# Z7_MGTX.net
KiCad netlist of a schematic drawn in Altium Designer
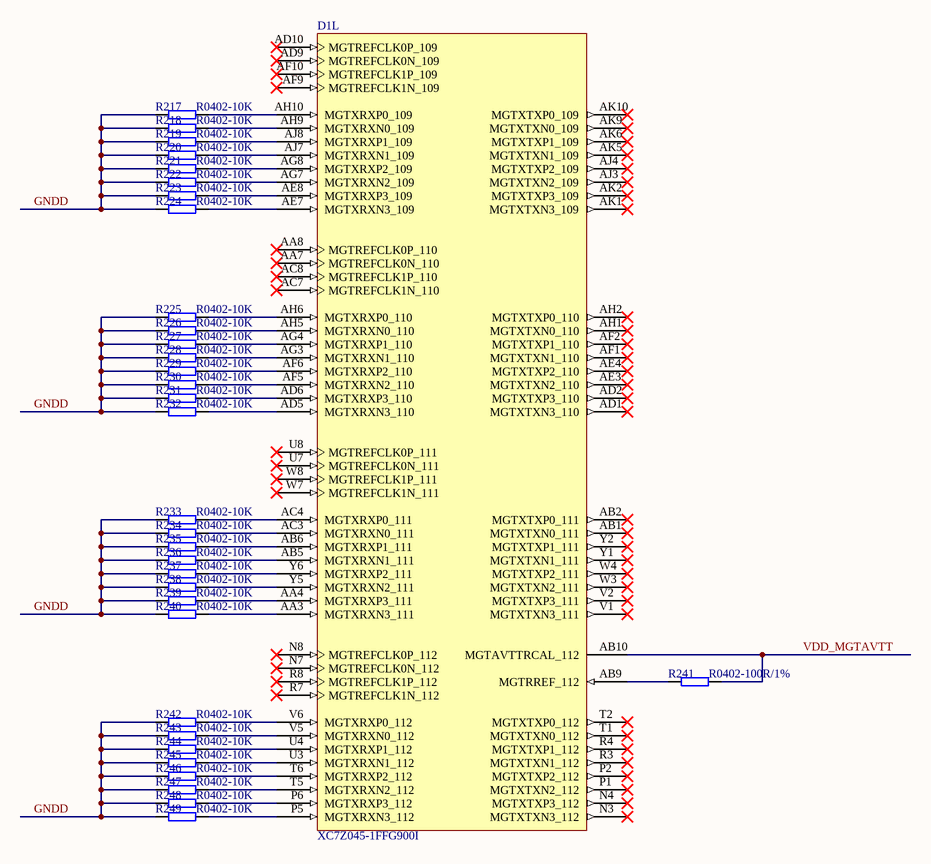
[diagram p0: Z7_MGTX.SchDoc]

(export (version "E")
  (design (tool "Eeschema 10.0.6"))
  (components
    (comp (ref "D1")
      (value "XC7Z045-1FFG900I")
      (footprint "FFG900")
      (fields (field (name "GENERIC PART NUMBER") "XC7Z045") (field (name "MANUFACTURER") "Xilinx"))
      (libsource (lib "Xilinx Zynq-7000") (part "XC7Z045-1FFG900I"))
    )
    (comp (ref "R217")
      (value "R0402-10K")
      (footprint "R0402")
      (fields (field (name "SCHEMATIC_PART") "RES") (field (name "MANUFACTURER") "SAMSUNG"))
      (libsource (lib "Database_Libs1") (part "RES"))
    )
    (comp (ref "R218")
      (value "R0402-10K")
      (footprint "R0402")
      (fields (field (name "SCHEMATIC_PART") "RES") (field (name "MANUFACTURER") "SAMSUNG"))
      (libsource (lib "Database_Libs1") (part "RES"))
    )
    (comp (ref "R219")
      (value "R0402-10K")
      (footprint "R0402")
      (fields (field (name "SCHEMATIC_PART") "RES") (field (name "MANUFACTURER") "SAMSUNG"))
      (libsource (lib "Database_Libs1") (part "RES"))
    )
    (comp (ref "R220")
      (value "R0402-10K")
      (footprint "R0402")
      (fields (field (name "SCHEMATIC_PART") "RES") (field (name "MANUFACTURER") "SAMSUNG"))
      (libsource (lib "Database_Libs1") (part "RES"))
    )
    (comp (ref "R221")
      (value "R0402-10K")
      (footprint "R0402")
      (fields (field (name "SCHEMATIC_PART") "RES") (field (name "MANUFACTURER") "SAMSUNG"))
      (libsource (lib "Database_Libs1") (part "RES"))
    )
    (comp (ref "R222")
      (value "R0402-10K")
      (footprint "R0402")
      (fields (field (name "SCHEMATIC_PART") "RES") (field (name "MANUFACTURER") "SAMSUNG"))
      (libsource (lib "Database_Libs1") (part "RES"))
    )
    (comp (ref "R223")
      (value "R0402-10K")
      (footprint "R0402")
      (fields (field (name "SCHEMATIC_PART") "RES") (field (name "MANUFACTURER") "SAMSUNG"))
      (libsource (lib "Database_Libs1") (part "RES"))
    )
    (comp (ref "R224")
      (value "R0402-10K")
      (footprint "R0402")
      (fields (field (name "SCHEMATIC_PART") "RES") (field (name "MANUFACTURER") "SAMSUNG"))
      (libsource (lib "Database_Libs1") (part "RES"))
    )
    (comp (ref "R225")
      (value "R0402-10K")
      (footprint "R0402")
      (fields (field (name "SCHEMATIC_PART") "RES") (field (name "MANUFACTURER") "SAMSUNG"))
      (libsource (lib "Database_Libs1") (part "RES"))
    )
    (comp (ref "R226")
      (value "R0402-10K")
      (footprint "R0402")
      (fields (field (name "SCHEMATIC_PART") "RES") (field (name "MANUFACTURER") "SAMSUNG"))
      (libsource (lib "Database_Libs1") (part "RES"))
    )
    (comp (ref "R227")
      (value "R0402-10K")
      (footprint "R0402")
      (fields (field (name "SCHEMATIC_PART") "RES") (field (name "MANUFACTURER") "SAMSUNG"))
      (libsource (lib "Database_Libs1") (part "RES"))
    )
    (comp (ref "R228")
      (value "R0402-10K")
      (footprint "R0402")
      (fields (field (name "SCHEMATIC_PART") "RES") (field (name "MANUFACTURER") "SAMSUNG"))
      (libsource (lib "Database_Libs1") (part "RES"))
    )
    (comp (ref "R229")
      (value "R0402-10K")
      (footprint "R0402")
      (fields (field (name "SCHEMATIC_PART") "RES") (field (name "MANUFACTURER") "SAMSUNG"))
      (libsource (lib "Database_Libs1") (part "RES"))
    )
    (comp (ref "R230")
      (value "R0402-10K")
      (footprint "R0402")
      (fields (field (name "SCHEMATIC_PART") "RES") (field (name "MANUFACTURER") "SAMSUNG"))
      (libsource (lib "Database_Libs1") (part "RES"))
    )
    (comp (ref "R231")
      (value "R0402-10K")
      (footprint "R0402")
      (fields (field (name "SCHEMATIC_PART") "RES") (field (name "MANUFACTURER") "SAMSUNG"))
      (libsource (lib "Database_Libs1") (part "RES"))
    )
    (comp (ref "R232")
      (value "R0402-10K")
      (footprint "R0402")
      (fields (field (name "SCHEMATIC_PART") "RES") (field (name "MANUFACTURER") "SAMSUNG"))
      (libsource (lib "Database_Libs1") (part "RES"))
    )
    (comp (ref "R233")
      (value "R0402-10K")
      (footprint "R0402")
      (fields (field (name "SCHEMATIC_PART") "RES") (field (name "MANUFACTURER") "SAMSUNG"))
      (libsource (lib "Database_Libs1") (part "RES"))
    )
    (comp (ref "R234")
      (value "R0402-10K")
      (footprint "R0402")
      (fields (field (name "SCHEMATIC_PART") "RES") (field (name "MANUFACTURER") "SAMSUNG"))
      (libsource (lib "Database_Libs1") (part "RES"))
    )
    (comp (ref "R235")
      (value "R0402-10K")
      (footprint "R0402")
      (fields (field (name "SCHEMATIC_PART") "RES") (field (name "MANUFACTURER") "SAMSUNG"))
      (libsource (lib "Database_Libs1") (part "RES"))
    )
    (comp (ref "R236")
      (value "R0402-10K")
      (footprint "R0402")
      (fields (field (name "SCHEMATIC_PART") "RES") (field (name "MANUFACTURER") "SAMSUNG"))
      (libsource (lib "Database_Libs1") (part "RES"))
    )
    (comp (ref "R237")
      (value "R0402-10K")
      (footprint "R0402")
      (fields (field (name "SCHEMATIC_PART") "RES") (field (name "MANUFACTURER") "SAMSUNG"))
      (libsource (lib "Database_Libs1") (part "RES"))
    )
    (comp (ref "R238")
      (value "R0402-10K")
      (footprint "R0402")
      (fields (field (name "SCHEMATIC_PART") "RES") (field (name "MANUFACTURER") "SAMSUNG"))
      (libsource (lib "Database_Libs1") (part "RES"))
    )
    (comp (ref "R239")
      (value "R0402-10K")
      (footprint "R0402")
      (fields (field (name "SCHEMATIC_PART") "RES") (field (name "MANUFACTURER") "SAMSUNG"))
      (libsource (lib "Database_Libs1") (part "RES"))
    )
    (comp (ref "R240")
      (value "R0402-10K")
      (footprint "R0402")
      (fields (field (name "SCHEMATIC_PART") "RES") (field (name "MANUFACTURER") "SAMSUNG"))
      (libsource (lib "Database_Libs1") (part "RES"))
    )
    (comp (ref "R241")
      (value "R0402-100R/1%")
      (footprint "R0402")
      (fields (field (name "SCHEMATIC_PART") "RES") (field (name "MANUFACTURER") "SAMSUNG"))
      (libsource (lib "Database_Libs1") (part "RES"))
    )
    (comp (ref "R242")
      (value "R0402-10K")
      (footprint "R0402")
      (fields (field (name "SCHEMATIC_PART") "RES") (field (name "MANUFACTURER") "SAMSUNG"))
      (libsource (lib "Database_Libs1") (part "RES"))
    )
    (comp (ref "R243")
      (value "R0402-10K")
      (footprint "R0402")
      (fields (field (name "SCHEMATIC_PART") "RES") (field (name "MANUFACTURER") "SAMSUNG"))
      (libsource (lib "Database_Libs1") (part "RES"))
    )
    (comp (ref "R244")
      (value "R0402-10K")
      (footprint "R0402")
      (fields (field (name "SCHEMATIC_PART") "RES") (field (name "MANUFACTURER") "SAMSUNG"))
      (libsource (lib "Database_Libs1") (part "RES"))
    )
    (comp (ref "R245")
      (value "R0402-10K")
      (footprint "R0402")
      (fields (field (name "SCHEMATIC_PART") "RES") (field (name "MANUFACTURER") "SAMSUNG"))
      (libsource (lib "Database_Libs1") (part "RES"))
    )
    (comp (ref "R246")
      (value "R0402-10K")
      (footprint "R0402")
      (fields (field (name "SCHEMATIC_PART") "RES") (field (name "MANUFACTURER") "SAMSUNG"))
      (libsource (lib "Database_Libs1") (part "RES"))
    )
    (comp (ref "R247")
      (value "R0402-10K")
      (footprint "R0402")
      (fields (field (name "SCHEMATIC_PART") "RES") (field (name "MANUFACTURER") "SAMSUNG"))
      (libsource (lib "Database_Libs1") (part "RES"))
    )
    (comp (ref "R248")
      (value "R0402-10K")
      (footprint "R0402")
      (fields (field (name "SCHEMATIC_PART") "RES") (field (name "MANUFACTURER") "SAMSUNG"))
      (libsource (lib "Database_Libs1") (part "RES"))
    )
    (comp (ref "R249")
      (value "R0402-10K")
      (footprint "R0402")
      (fields (field (name "SCHEMATIC_PART") "RES") (field (name "MANUFACTURER") "SAMSUNG"))
      (libsource (lib "Database_Libs1") (part "RES"))
    )
  )
  (nets
    (net (code "1") (name "/GNDD") (class "Default")
      (node (ref "R217") (pin "2") (pintype "passive"))
      (node (ref "R218") (pin "2") (pintype "passive"))
      (node (ref "R219") (pin "2") (pintype "passive"))
      (node (ref "R220") (pin "2") (pintype "passive"))
      (node (ref "R221") (pin "2") (pintype "passive"))
      (node (ref "R222") (pin "2") (pintype "passive"))
      (node (ref "R223") (pin "2") (pintype "passive"))
      (node (ref "R224") (pin "2") (pintype "passive"))
      (node (ref "R225") (pin "2") (pintype "passive"))
      (node (ref "R226") (pin "2") (pintype "passive"))
      (node (ref "R227") (pin "2") (pintype "passive"))
      (node (ref "R228") (pin "2") (pintype "passive"))
      (node (ref "R229") (pin "2") (pintype "passive"))
      (node (ref "R230") (pin "2") (pintype "passive"))
      (node (ref "R231") (pin "2") (pintype "passive"))
      (node (ref "R232") (pin "2") (pintype "passive"))
      (node (ref "R233") (pin "2") (pintype "passive"))
      (node (ref "R234") (pin "2") (pintype "passive"))
      (node (ref "R235") (pin "2") (pintype "passive"))
      (node (ref "R236") (pin "2") (pintype "passive"))
      (node (ref "R237") (pin "2") (pintype "passive"))
      (node (ref "R238") (pin "2") (pintype "passive"))
      (node (ref "R239") (pin "2") (pintype "passive"))
      (node (ref "R240") (pin "2") (pintype "passive"))
      (node (ref "R242") (pin "2") (pintype "passive"))
      (node (ref "R243") (pin "2") (pintype "passive"))
      (node (ref "R244") (pin "2") (pintype "passive"))
      (node (ref "R245") (pin "2") (pintype "passive"))
      (node (ref "R246") (pin "2") (pintype "passive"))
      (node (ref "R247") (pin "2") (pintype "passive"))
      (node (ref "R248") (pin "2") (pintype "passive"))
      (node (ref "R249") (pin "2") (pintype "passive"))
    )
    (net (code "2") (name "/VDD_MGTAVTT") (class "Default")
      (node (ref "D1") (pin "AB10") (pinfunction "MGTAVTTRCAL_112_AB10") (pintype "passive"))
      (node (ref "R241") (pin "1") (pintype "passive"))
    )
    (net (code "3") (name "Net-(D1L-MGTRREF_112)") (class "Default")
      (node (ref "D1") (pin "AB9") (pinfunction "MGTRREF_112_AB9") (pintype "input"))
      (node (ref "R241") (pin "2") (pintype "passive"))
    )
    (net (code "4") (name "Net-(D1L-MGTXRXN0_109)") (class "Default")
      (node (ref "D1") (pin "AH9") (pinfunction "MGTXRXN0_109_AH9") (pintype "input"))
      (node (ref "R218") (pin "1") (pintype "passive"))
    )
    (net (code "5") (name "Net-(D1L-MGTXRXN0_110)") (class "Default")
      (node (ref "D1") (pin "AH5") (pinfunction "MGTXRXN0_110_AH5") (pintype "input"))
      (node (ref "R226") (pin "1") (pintype "passive"))
    )
    (net (code "6") (name "Net-(D1L-MGTXRXN0_111)") (class "Default")
      (node (ref "D1") (pin "AC3") (pinfunction "MGTXRXN0_111_AC3") (pintype "input"))
      (node (ref "R234") (pin "1") (pintype "passive"))
    )
    (net (code "7") (name "Net-(D1L-MGTXRXN0_112)") (class "Default")
      (node (ref "D1") (pin "V5") (pinfunction "MGTXRXN0_112_V5") (pintype "input"))
      (node (ref "R243") (pin "1") (pintype "passive"))
    )
    (net (code "8") (name "Net-(D1L-MGTXRXN1_109)") (class "Default")
      (node (ref "D1") (pin "AJ7") (pinfunction "MGTXRXN1_109_AJ7") (pintype "input"))
      (node (ref "R220") (pin "1") (pintype "passive"))
    )
    (net (code "9") (name "Net-(D1L-MGTXRXN1_110)") (class "Default")
      (node (ref "D1") (pin "AG3") (pinfunction "MGTXRXN1_110_AG3") (pintype "input"))
      (node (ref "R228") (pin "1") (pintype "passive"))
    )
    (net (code "10") (name "Net-(D1L-MGTXRXN1_111)") (class "Default")
      (node (ref "D1") (pin "AB5") (pinfunction "MGTXRXN1_111_AB5") (pintype "input"))
      (node (ref "R236") (pin "1") (pintype "passive"))
    )
    (net (code "11") (name "Net-(D1L-MGTXRXN1_112)") (class "Default")
      (node (ref "D1") (pin "U3") (pinfunction "MGTXRXN1_112_U3") (pintype "input"))
      (node (ref "R245") (pin "1") (pintype "passive"))
    )
    (net (code "12") (name "Net-(D1L-MGTXRXN2_109)") (class "Default")
      (node (ref "D1") (pin "AG7") (pinfunction "MGTXRXN2_109_AG7") (pintype "input"))
      (node (ref "R222") (pin "1") (pintype "passive"))
    )
    (net (code "13") (name "Net-(D1L-MGTXRXN2_110)") (class "Default")
      (node (ref "D1") (pin "AF5") (pinfunction "MGTXRXN2_110_AF5") (pintype "input"))
      (node (ref "R230") (pin "1") (pintype "passive"))
    )
    (net (code "14") (name "Net-(D1L-MGTXRXN2_111)") (class "Default")
      (node (ref "D1") (pin "Y5") (pinfunction "MGTXRXN2_111_Y5") (pintype "input"))
      (node (ref "R238") (pin "1") (pintype "passive"))
    )
    (net (code "15") (name "Net-(D1L-MGTXRXN2_112)") (class "Default")
      (node (ref "D1") (pin "T5") (pinfunction "MGTXRXN2_112_T5") (pintype "input"))
      (node (ref "R247") (pin "1") (pintype "passive"))
    )
    (net (code "16") (name "Net-(D1L-MGTXRXN3_109)") (class "Default")
      (node (ref "D1") (pin "AE7") (pinfunction "MGTXRXN3_109_AE7") (pintype "input"))
      (node (ref "R224") (pin "1") (pintype "passive"))
    )
    (net (code "17") (name "Net-(D1L-MGTXRXN3_110)") (class "Default")
      (node (ref "D1") (pin "AD5") (pinfunction "MGTXRXN3_110_AD5") (pintype "input"))
      (node (ref "R232") (pin "1") (pintype "passive"))
    )
    (net (code "18") (name "Net-(D1L-MGTXRXN3_111)") (class "Default")
      (node (ref "D1") (pin "AA3") (pinfunction "MGTXRXN3_111_AA3") (pintype "input"))
      (node (ref "R240") (pin "1") (pintype "passive"))
    )
    (net (code "19") (name "Net-(D1L-MGTXRXN3_112)") (class "Default")
      (node (ref "D1") (pin "P5") (pinfunction "MGTXRXN3_112_P5") (pintype "input"))
      (node (ref "R249") (pin "1") (pintype "passive"))
    )
    (net (code "20") (name "Net-(D1L-MGTXRXP0_109)") (class "Default")
      (node (ref "D1") (pin "AH10") (pinfunction "MGTXRXP0_109_AH10") (pintype "input"))
      (node (ref "R217") (pin "1") (pintype "passive"))
    )
    (net (code "21") (name "Net-(D1L-MGTXRXP0_110)") (class "Default")
      (node (ref "D1") (pin "AH6") (pinfunction "MGTXRXP0_110_AH6") (pintype "input"))
      (node (ref "R225") (pin "1") (pintype "passive"))
    )
    (net (code "22") (name "Net-(D1L-MGTXRXP0_111)") (class "Default")
      (node (ref "D1") (pin "AC4") (pinfunction "MGTXRXP0_111_AC4") (pintype "input"))
      (node (ref "R233") (pin "1") (pintype "passive"))
    )
    (net (code "23") (name "Net-(D1L-MGTXRXP0_112)") (class "Default")
      (node (ref "D1") (pin "V6") (pinfunction "MGTXRXP0_112_V6") (pintype "input"))
      (node (ref "R242") (pin "1") (pintype "passive"))
    )
    (net (code "24") (name "Net-(D1L-MGTXRXP1_109)") (class "Default")
      (node (ref "D1") (pin "AJ8") (pinfunction "MGTXRXP1_109_AJ8") (pintype "input"))
      (node (ref "R219") (pin "1") (pintype "passive"))
    )
    (net (code "25") (name "Net-(D1L-MGTXRXP1_110)") (class "Default")
      (node (ref "D1") (pin "AG4") (pinfunction "MGTXRXP1_110_AG4") (pintype "input"))
      (node (ref "R227") (pin "1") (pintype "passive"))
    )
    (net (code "26") (name "Net-(D1L-MGTXRXP1_111)") (class "Default")
      (node (ref "D1") (pin "AB6") (pinfunction "MGTXRXP1_111_AB6") (pintype "input"))
      (node (ref "R235") (pin "1") (pintype "passive"))
    )
    (net (code "27") (name "Net-(D1L-MGTXRXP1_112)") (class "Default")
      (node (ref "D1") (pin "U4") (pinfunction "MGTXRXP1_112_U4") (pintype "input"))
      (node (ref "R244") (pin "1") (pintype "passive"))
    )
    (net (code "28") (name "Net-(D1L-MGTXRXP2_109)") (class "Default")
      (node (ref "D1") (pin "AG8") (pinfunction "MGTXRXP2_109_AG8") (pintype "input"))
      (node (ref "R221") (pin "1") (pintype "passive"))
    )
    (net (code "29") (name "Net-(D1L-MGTXRXP2_110)") (class "Default")
      (node (ref "D1") (pin "AF6") (pinfunction "MGTXRXP2_110_AF6") (pintype "input"))
      (node (ref "R229") (pin "1") (pintype "passive"))
    )
    (net (code "30") (name "Net-(D1L-MGTXRXP2_111)") (class "Default")
      (node (ref "D1") (pin "Y6") (pinfunction "MGTXRXP2_111_Y6") (pintype "input"))
      (node (ref "R237") (pin "1") (pintype "passive"))
    )
    (net (code "31") (name "Net-(D1L-MGTXRXP2_112)") (class "Default")
      (node (ref "D1") (pin "T6") (pinfunction "MGTXRXP2_112_T6") (pintype "input"))
      (node (ref "R246") (pin "1") (pintype "passive"))
    )
    (net (code "32") (name "Net-(D1L-MGTXRXP3_109)") (class "Default")
      (node (ref "D1") (pin "AE8") (pinfunction "MGTXRXP3_109_AE8") (pintype "input"))
      (node (ref "R223") (pin "1") (pintype "passive"))
    )
    (net (code "33") (name "Net-(D1L-MGTXRXP3_110)") (class "Default")
      (node (ref "D1") (pin "AD6") (pinfunction "MGTXRXP3_110_AD6") (pintype "input"))
      (node (ref "R231") (pin "1") (pintype "passive"))
    )
    (net (code "34") (name "Net-(D1L-MGTXRXP3_111)") (class "Default")
      (node (ref "D1") (pin "AA4") (pinfunction "MGTXRXP3_111_AA4") (pintype "input"))
      (node (ref "R239") (pin "1") (pintype "passive"))
    )
    (net (code "35") (name "Net-(D1L-MGTXRXP3_112)") (class "Default")
      (node (ref "D1") (pin "P6") (pinfunction "MGTXRXP3_112_P6") (pintype "input"))
      (node (ref "R248") (pin "1") (pintype "passive"))
    )
    (net (code "36") (name "unconnected-(D1L-MGTREFCLK0N_109-PadAD9)") (class "Default")
      (node (ref "D1") (pin "AD9") (pinfunction "MGTREFCLK0N_109_AD9") (pintype "input+no_connect"))
    )
    (net (code "37") (name "unconnected-(D1L-MGTREFCLK0N_110-PadAA7)") (class "Default")
      (node (ref "D1") (pin "AA7") (pinfunction "MGTREFCLK0N_110_AA7") (pintype "input+no_connect"))
    )
    (net (code "38") (name "unconnected-(D1L-MGTREFCLK0N_111-PadU7)") (class "Default")
      (node (ref "D1") (pin "U7") (pinfunction "MGTREFCLK0N_111_U7") (pintype "input+no_connect"))
    )
    (net (code "39") (name "unconnected-(D1L-MGTREFCLK0N_112-PadN7)") (class "Default")
      (node (ref "D1") (pin "N7") (pinfunction "MGTREFCLK0N_112_N7") (pintype "input+no_connect"))
    )
    (net (code "40") (name "unconnected-(D1L-MGTREFCLK0P_109-PadAD10)") (class "Default")
      (node (ref "D1") (pin "AD10") (pinfunction "MGTREFCLK0P_109_AD10") (pintype "input+no_connect"))
    )
    (net (code "41") (name "unconnected-(D1L-MGTREFCLK0P_110-PadAA8)") (class "Default")
      (node (ref "D1") (pin "AA8") (pinfunction "MGTREFCLK0P_110_AA8") (pintype "input+no_connect"))
    )
    (net (code "42") (name "unconnected-(D1L-MGTREFCLK0P_111-PadU8)") (class "Default")
      (node (ref "D1") (pin "U8") (pinfunction "MGTREFCLK0P_111_U8") (pintype "input+no_connect"))
    )
    (net (code "43") (name "unconnected-(D1L-MGTREFCLK0P_112-PadN8)") (class "Default")
      (node (ref "D1") (pin "N8") (pinfunction "MGTREFCLK0P_112_N8") (pintype "input+no_connect"))
    )
    (net (code "44") (name "unconnected-(D1L-MGTREFCLK1N_109-PadAF9)") (class "Default")
      (node (ref "D1") (pin "AF9") (pinfunction "MGTREFCLK1N_109_AF9") (pintype "input+no_connect"))
    )
    (net (code "45") (name "unconnected-(D1L-MGTREFCLK1N_110-PadAC7)") (class "Default")
      (node (ref "D1") (pin "AC7") (pinfunction "MGTREFCLK1N_110_AC7") (pintype "input+no_connect"))
    )
    (net (code "46") (name "unconnected-(D1L-MGTREFCLK1N_111-PadW7)") (class "Default")
      (node (ref "D1") (pin "W7") (pinfunction "MGTREFCLK1N_111_W7") (pintype "input+no_connect"))
    )
    (net (code "47") (name "unconnected-(D1L-MGTREFCLK1N_112-PadR7)") (class "Default")
      (node (ref "D1") (pin "R7") (pinfunction "MGTREFCLK1N_112_R7") (pintype "input+no_connect"))
    )
    (net (code "48") (name "unconnected-(D1L-MGTREFCLK1P_109-PadAF10)") (class "Default")
      (node (ref "D1") (pin "AF10") (pinfunction "MGTREFCLK1P_109_AF10") (pintype "input+no_connect"))
    )
    (net (code "49") (name "unconnected-(D1L-MGTREFCLK1P_110-PadAC8)") (class "Default")
      (node (ref "D1") (pin "AC8") (pinfunction "MGTREFCLK1P_110_AC8") (pintype "input+no_connect"))
    )
    (net (code "50") (name "unconnected-(D1L-MGTREFCLK1P_111-PadW8)") (class "Default")
      (node (ref "D1") (pin "W8") (pinfunction "MGTREFCLK1P_111_W8") (pintype "input+no_connect"))
    )
    (net (code "51") (name "unconnected-(D1L-MGTREFCLK1P_112-PadR8)") (class "Default")
      (node (ref "D1") (pin "R8") (pinfunction "MGTREFCLK1P_112_R8") (pintype "input+no_connect"))
    )
    (net (code "52") (name "unconnected-(D1L-MGTXTXN0_109-PadAK9)") (class "Default")
      (node (ref "D1") (pin "AK9") (pinfunction "MGTXTXN0_109_AK9") (pintype "output+no_connect"))
    )
    (net (code "53") (name "unconnected-(D1L-MGTXTXN0_110-PadAH1)") (class "Default")
      (node (ref "D1") (pin "AH1") (pinfunction "MGTXTXN0_110_AH1") (pintype "output+no_connect"))
    )
    (net (code "54") (name "unconnected-(D1L-MGTXTXN0_111-PadAB1)") (class "Default")
      (node (ref "D1") (pin "AB1") (pinfunction "MGTXTXN0_111_AB1") (pintype "output+no_connect"))
    )
    (net (code "55") (name "unconnected-(D1L-MGTXTXN0_112-PadT1)") (class "Default")
      (node (ref "D1") (pin "T1") (pinfunction "MGTXTXN0_112_T1") (pintype "output+no_connect"))
    )
    (net (code "56") (name "unconnected-(D1L-MGTXTXN1_109-PadAK5)") (class "Default")
      (node (ref "D1") (pin "AK5") (pinfunction "MGTXTXN1_109_AK5") (pintype "output+no_connect"))
    )
    (net (code "57") (name "unconnected-(D1L-MGTXTXN1_110-PadAF1)") (class "Default")
      (node (ref "D1") (pin "AF1") (pinfunction "MGTXTXN1_110_AF1") (pintype "output+no_connect"))
    )
    (net (code "58") (name "unconnected-(D1L-MGTXTXN1_111-PadY1)") (class "Default")
      (node (ref "D1") (pin "Y1") (pinfunction "MGTXTXN1_111_Y1") (pintype "output+no_connect"))
    )
    (net (code "59") (name "unconnected-(D1L-MGTXTXN1_112-PadR3)") (class "Default")
      (node (ref "D1") (pin "R3") (pinfunction "MGTXTXN1_112_R3") (pintype "output+no_connect"))
    )
    (net (code "60") (name "unconnected-(D1L-MGTXTXN2_109-PadAJ3)") (class "Default")
      (node (ref "D1") (pin "AJ3") (pinfunction "MGTXTXN2_109_AJ3") (pintype "output+no_connect"))
    )
    (net (code "61") (name "unconnected-(D1L-MGTXTXN2_110-PadAE3)") (class "Default")
      (node (ref "D1") (pin "AE3") (pinfunction "MGTXTXN2_110_AE3") (pintype "output+no_connect"))
    )
    (net (code "62") (name "unconnected-(D1L-MGTXTXN2_111-PadW3)") (class "Default")
      (node (ref "D1") (pin "W3") (pinfunction "MGTXTXN2_111_W3") (pintype "output+no_connect"))
    )
    (net (code "63") (name "unconnected-(D1L-MGTXTXN2_112-PadP1)") (class "Default")
      (node (ref "D1") (pin "P1") (pinfunction "MGTXTXN2_112_P1") (pintype "output+no_connect"))
    )
    (net (code "64") (name "unconnected-(D1L-MGTXTXN3_109-PadAK1)") (class "Default")
      (node (ref "D1") (pin "AK1") (pinfunction "MGTXTXN3_109_AK1") (pintype "output+no_connect"))
    )
    (net (code "65") (name "unconnected-(D1L-MGTXTXN3_110-PadAD1)") (class "Default")
      (node (ref "D1") (pin "AD1") (pinfunction "MGTXTXN3_110_AD1") (pintype "output+no_connect"))
    )
    (net (code "66") (name "unconnected-(D1L-MGTXTXN3_111-PadV1)") (class "Default")
      (node (ref "D1") (pin "V1") (pinfunction "MGTXTXN3_111_V1") (pintype "output+no_connect"))
    )
    (net (code "67") (name "unconnected-(D1L-MGTXTXN3_112-PadN3)") (class "Default")
      (node (ref "D1") (pin "N3") (pinfunction "MGTXTXN3_112_N3") (pintype "output+no_connect"))
    )
    (net (code "68") (name "unconnected-(D1L-MGTXTXP0_109-PadAK10)") (class "Default")
      (node (ref "D1") (pin "AK10") (pinfunction "MGTXTXP0_109_AK10") (pintype "output+no_connect"))
    )
    (net (code "69") (name "unconnected-(D1L-MGTXTXP0_110-PadAH2)") (class "Default")
      (node (ref "D1") (pin "AH2") (pinfunction "MGTXTXP0_110_AH2") (pintype "output+no_connect"))
    )
    (net (code "70") (name "unconnected-(D1L-MGTXTXP0_111-PadAB2)") (class "Default")
      (node (ref "D1") (pin "AB2") (pinfunction "MGTXTXP0_111_AB2") (pintype "output+no_connect"))
    )
    (net (code "71") (name "unconnected-(D1L-MGTXTXP0_112-PadT2)") (class "Default")
      (node (ref "D1") (pin "T2") (pinfunction "MGTXTXP0_112_T2") (pintype "output+no_connect"))
    )
    (net (code "72") (name "unconnected-(D1L-MGTXTXP1_109-PadAK6)") (class "Default")
      (node (ref "D1") (pin "AK6") (pinfunction "MGTXTXP1_109_AK6") (pintype "output+no_connect"))
    )
    (net (code "73") (name "unconnected-(D1L-MGTXTXP1_110-PadAF2)") (class "Default")
      (node (ref "D1") (pin "AF2") (pinfunction "MGTXTXP1_110_AF2") (pintype "output+no_connect"))
    )
    (net (code "74") (name "unconnected-(D1L-MGTXTXP1_111-PadY2)") (class "Default")
      (node (ref "D1") (pin "Y2") (pinfunction "MGTXTXP1_111_Y2") (pintype "output+no_connect"))
    )
    (net (code "75") (name "unconnected-(D1L-MGTXTXP1_112-PadR4)") (class "Default")
      (node (ref "D1") (pin "R4") (pinfunction "MGTXTXP1_112_R4") (pintype "output+no_connect"))
    )
    (net (code "76") (name "unconnected-(D1L-MGTXTXP2_109-PadAJ4)") (class "Default")
      (node (ref "D1") (pin "AJ4") (pinfunction "MGTXTXP2_109_AJ4") (pintype "output+no_connect"))
    )
    (net (code "77") (name "unconnected-(D1L-MGTXTXP2_110-PadAE4)") (class "Default")
      (node (ref "D1") (pin "AE4") (pinfunction "MGTXTXP2_110_AE4") (pintype "output+no_connect"))
    )
    (net (code "78") (name "unconnected-(D1L-MGTXTXP2_111-PadW4)") (class "Default")
      (node (ref "D1") (pin "W4") (pinfunction "MGTXTXP2_111_W4") (pintype "output+no_connect"))
    )
    (net (code "79") (name "unconnected-(D1L-MGTXTXP2_112-PadP2)") (class "Default")
      (node (ref "D1") (pin "P2") (pinfunction "MGTXTXP2_112_P2") (pintype "output+no_connect"))
    )
    (net (code "80") (name "unconnected-(D1L-MGTXTXP3_109-PadAK2)") (class "Default")
      (node (ref "D1") (pin "AK2") (pinfunction "MGTXTXP3_109_AK2") (pintype "output+no_connect"))
    )
    (net (code "81") (name "unconnected-(D1L-MGTXTXP3_110-PadAD2)") (class "Default")
      (node (ref "D1") (pin "AD2") (pinfunction "MGTXTXP3_110_AD2") (pintype "output+no_connect"))
    )
    (net (code "82") (name "unconnected-(D1L-MGTXTXP3_111-PadV2)") (class "Default")
      (node (ref "D1") (pin "V2") (pinfunction "MGTXTXP3_111_V2") (pintype "output+no_connect"))
    )
    (net (code "83") (name "unconnected-(D1L-MGTXTXP3_112-PadN4)") (class "Default")
      (node (ref "D1") (pin "N4") (pinfunction "MGTXTXP3_112_N4") (pintype "output+no_connect"))
    )
  )
)
